# 08_Peripherals.net
KiCad netlist of a schematic drawn in Altium Designer
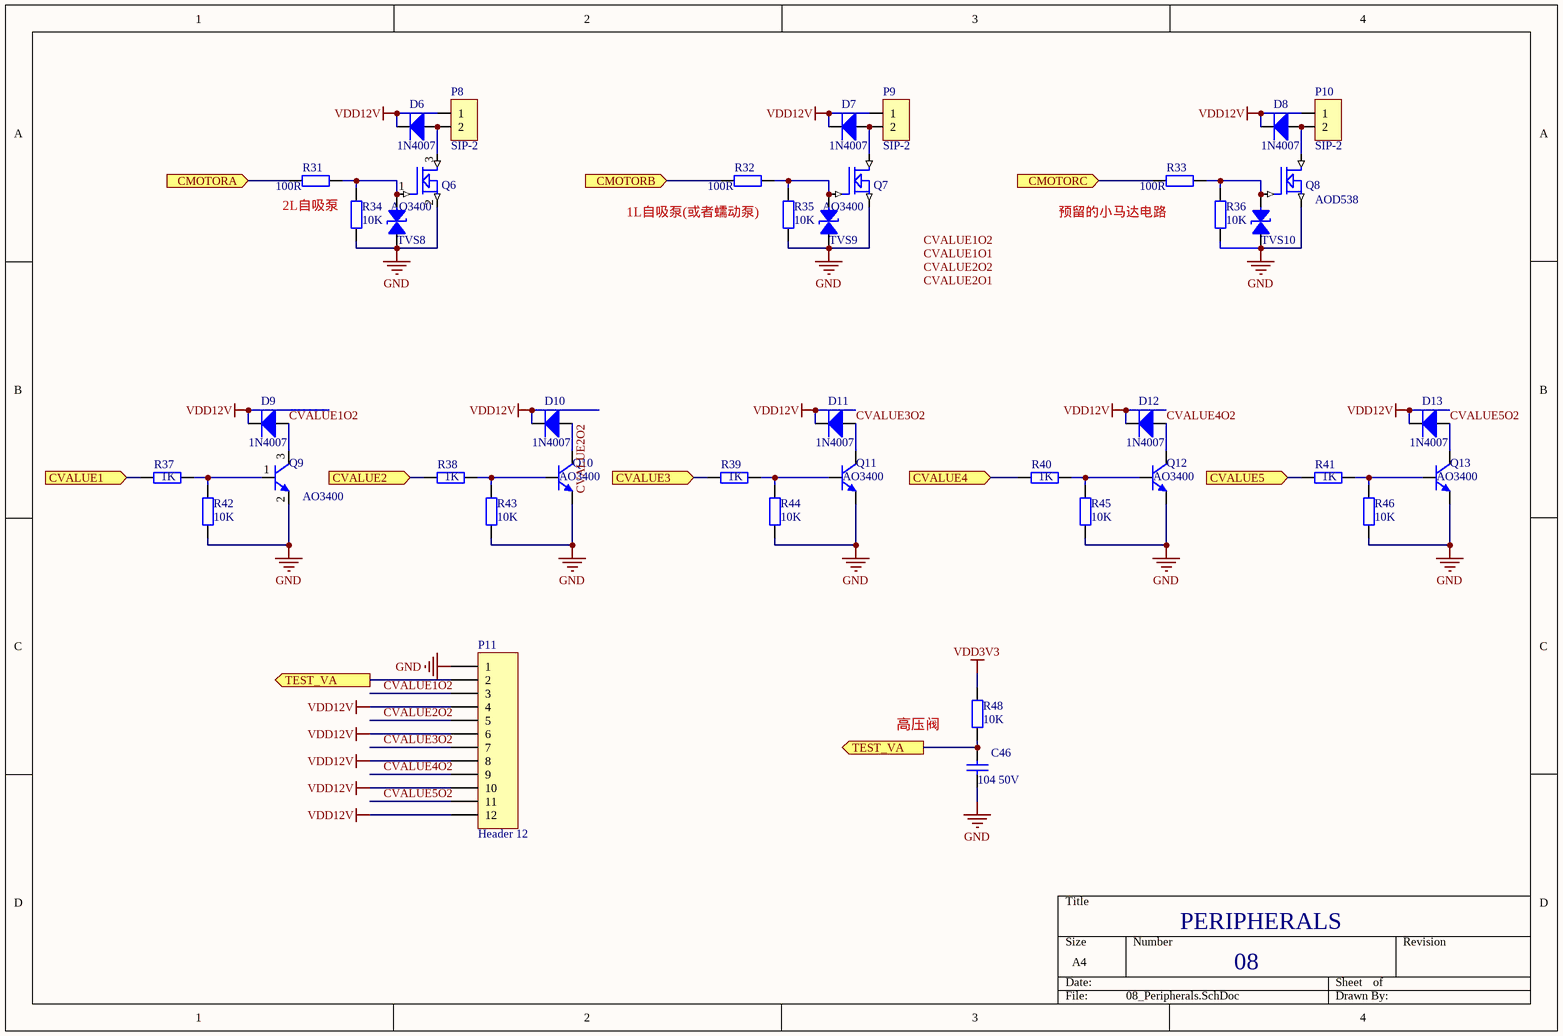
[diagram p0: 08_Peripherals.SchDoc]

(export (version "E")
  (design (tool "Eeschema 10.0.6"))
  (components
    (comp (ref "C46")
      (value "104 50V")
      (footprint "SMD-0603C")
      (description "贴片电容 10%")
      (libsource (lib "XiaoyI") (part "CAP4"))
    )
    (comp (ref "D6")
      (value "1N4007")
      (footprint "DO-214-AC")
      (description "贴片二极管")
      (libsource (lib "XiaoyI") (part "DIODE2"))
    )
    (comp (ref "D7")
      (value "1N4007")
      (footprint "DO-214-AC")
      (description "贴片二极管")
      (libsource (lib "XiaoyI") (part "DIODE2"))
    )
    (comp (ref "D8")
      (value "1N4007")
      (footprint "DO-214-AC")
      (description "贴片二极管")
      (libsource (lib "XiaoyI") (part "DIODE2"))
    )
    (comp (ref "D9")
      (value "1N4007")
      (footprint "DO-214-AC")
      (description "贴片二极管")
      (libsource (lib "XiaoyI") (part "DIODE2"))
    )
    (comp (ref "D10")
      (value "1N4007")
      (footprint "DO-214-AC")
      (description "贴片二极管")
      (libsource (lib "XiaoyI") (part "DIODE2"))
    )
    (comp (ref "D11")
      (value "1N4007")
      (footprint "DO-214-AC")
      (description "贴片二极管")
      (libsource (lib "XiaoyI") (part "DIODE2"))
    )
    (comp (ref "D12")
      (value "1N4007")
      (footprint "DO-214-AC")
      (description "贴片二极管")
      (libsource (lib "XiaoyI") (part "DIODE2"))
    )
    (comp (ref "D13")
      (value "1N4007")
      (footprint "DO-214-AC")
      (description "贴片二极管")
      (libsource (lib "XiaoyI") (part "DIODE2"))
    )
    (comp (ref "P8")
      (value "SIP-2")
      (footprint "SIP-2A")
      (description "XH2.54 2P 立贴")
      (libsource (lib "XiaoyI") (part "SIP-2"))
    )
    (comp (ref "P9")
      (value "SIP-2")
      (footprint "SIP-2A")
      (description "XH2.54 2P 立贴")
      (libsource (lib "XiaoyI") (part "SIP-2"))
    )
    (comp (ref "P10")
      (value "SIP-2")
      (footprint "VH-AW-3.96*2P")
      (description "XH2.54 2P 立贴")
      (libsource (lib "XiaoyI") (part "SIP-2"))
    )
    (comp (ref "P11")
      (value "Header 12")
      (footprint "12X2.54MMZ")
      (description "Header, 12-Pin")
      (fields (field (name "PUBLISHER") "Altium Limited"))
      (libsource (lib "Miscellaneous Connectors") (part "Header 12"))
    )
    (comp (ref "Q6")
      (value "AO3400")
      (footprint "SOT-23")
      (description "MOSFET N")
      (libsource (lib "") (part "MOSFET N_1"))
    )
    (comp (ref "Q7")
      (value "AO3400")
      (footprint "SOT-23")
      (description "MOSFET N")
      (libsource (lib "XiaoyI") (part "MOSFET N"))
    )
    (comp (ref "Q8")
      (value "AOD538")
      (footprint "TO252")
      (description "MOSFET N")
      (libsource (lib "XiaoyI") (part "MOSFET N"))
    )
    (comp (ref "Q9")
      (value "AO3400")
      (footprint "SOT-23")
      (description "三极管")
      (libsource (lib "") (part "NPN-1_1"))
    )
    (comp (ref "Q10")
      (value "AO3400")
      (footprint "SOT-23")
      (description "三极管")
      (libsource (lib "XiaoyI") (part "NPN-1"))
    )
    (comp (ref "Q11")
      (value "AO3400")
      (footprint "SOT-23")
      (description "三极管")
      (libsource (lib "XiaoyI") (part "NPN-1"))
    )
    (comp (ref "Q12")
      (value "AO3400")
      (footprint "SOT-23")
      (description "三极管")
      (libsource (lib "XiaoyI") (part "NPN-1"))
    )
    (comp (ref "Q13")
      (value "AO3400")
      (footprint "SOT-23")
      (description "三极管")
      (libsource (lib "XiaoyI") (part "NPN-1"))
    )
    (comp (ref "R31")
      (value "100R")
      (footprint "SMD-0603")
      (description "贴片电阻 5%")
      (libsource (lib "XiaoyI") (part "RES-SOP"))
    )
    (comp (ref "R32")
      (value "100R")
      (footprint "SMD-0603")
      (description "贴片电阻 5%")
      (libsource (lib "XiaoyI") (part "RES-SOP"))
    )
    (comp (ref "R33")
      (value "100R")
      (footprint "SMD-0603")
      (description "贴片电阻 5%")
      (libsource (lib "XiaoyI") (part "RES-SOP"))
    )
    (comp (ref "R34")
      (value "10K")
      (footprint "SMD-0603")
      (description "贴片电阻 5%")
      (libsource (lib "") (part "RES-SOP_1"))
    )
    (comp (ref "R35")
      (value "10K")
      (footprint "SMD-0603")
      (description "贴片电阻 5%")
      (libsource (lib "") (part "RES-SOP_1"))
    )
    (comp (ref "R36")
      (value "10K")
      (footprint "SMD-0603")
      (description "贴片电阻 5%")
      (libsource (lib "") (part "RES-SOP_1"))
    )
    (comp (ref "R37")
      (value "1K")
      (footprint "SMD-0603")
      (description "贴片电阻 5%")
      (libsource (lib "XiaoyI") (part "RES-SOP"))
    )
    (comp (ref "R38")
      (value "1K")
      (footprint "SMD-0603")
      (description "贴片电阻 5%")
      (libsource (lib "XiaoyI") (part "RES-SOP"))
    )
    (comp (ref "R39")
      (value "1K")
      (footprint "SMD-0603")
      (description "贴片电阻 5%")
      (libsource (lib "XiaoyI") (part "RES-SOP"))
    )
    (comp (ref "R40")
      (value "1K")
      (footprint "SMD-0603")
      (description "贴片电阻 5%")
      (libsource (lib "XiaoyI") (part "RES-SOP"))
    )
    (comp (ref "R41")
      (value "1K")
      (footprint "SMD-0603")
      (description "贴片电阻 5%")
      (libsource (lib "XiaoyI") (part "RES-SOP"))
    )
    (comp (ref "R42")
      (value "10K")
      (footprint "SMD-0603")
      (description "贴片电阻 5%")
      (libsource (lib "") (part "RES-SOP_1"))
    )
    (comp (ref "R43")
      (value "10K")
      (footprint "SMD-0603")
      (description "贴片电阻 5%")
      (libsource (lib "") (part "RES-SOP_1"))
    )
    (comp (ref "R44")
      (value "10K")
      (footprint "SMD-0603")
      (description "贴片电阻 5%")
      (libsource (lib "") (part "RES-SOP_1"))
    )
    (comp (ref "R45")
      (value "10K")
      (footprint "SMD-0603")
      (description "贴片电阻 5%")
      (libsource (lib "") (part "RES-SOP_1"))
    )
    (comp (ref "R46")
      (value "10K")
      (footprint "SMD-0603")
      (description "贴片电阻 5%")
      (libsource (lib "") (part "RES-SOP_1"))
    )
    (comp (ref "R48")
      (value "10K")
      (footprint "SMD-0603")
      (description "贴片电阻 5%")
      (libsource (lib "") (part "RES-SOP_2"))
    )
    (comp (ref "TVS8")
      (value "ESD5Z5.0CT1G")
      (footprint "SOD-523")
      (description "TVS")
      (libsource (lib "XiaoyI") (part "TVS-1"))
    )
    (comp (ref "TVS9")
      (value "ESD5Z5.0CT1G")
      (footprint "SOD-523")
      (description "TVS")
      (libsource (lib "XiaoyI") (part "TVS-1"))
    )
    (comp (ref "TVS10")
      (value "ESD5Z5.0CT1G")
      (footprint "SOD-523")
      (description "TVS")
      (libsource (lib "XiaoyI") (part "TVS-1"))
    )
  )
  (nets
    (net (code "1") (name "/CMOTORA") (class "Default")
      (node (ref "R31") (pin "2") (pinfunction "2_2") (pintype "passive"))
    )
    (net (code "2") (name "/CMOTORB") (class "Default")
      (node (ref "R32") (pin "2") (pinfunction "2_2") (pintype "passive"))
    )
    (net (code "3") (name "/CMOTORC") (class "Default")
      (node (ref "R33") (pin "2") (pinfunction "2_2") (pintype "passive"))
    )
    (net (code "4") (name "/CVALUE1") (class "Default")
      (node (ref "R37") (pin "2") (pinfunction "2_2") (pintype "passive"))
    )
    (net (code "6") (name "/CVALUE1O2") (class "Default")
      (node (ref "D9") (pin "1") (pinfunction "A_1") (pintype "passive"))
      (node (ref "P11") (pin "3") (pinfunction "3_3") (pintype "passive"))
      (node (ref "Q9") (pin "3") (pinfunction "C_3") (pintype "passive"))
    )
    (net (code "7") (name "/CVALUE2") (class "Default")
      (node (ref "R38") (pin "2") (pinfunction "2_2") (pintype "passive"))
    )
    (net (code "9") (name "/CVALUE2O2") (class "Default")
      (node (ref "D10") (pin "1") (pinfunction "A_1") (pintype "passive"))
      (node (ref "P11") (pin "5") (pinfunction "5_5") (pintype "passive"))
      (node (ref "Q10") (pin "3") (pinfunction "C_3") (pintype "passive"))
    )
    (net (code "10") (name "/CVALUE3") (class "Default")
      (node (ref "R39") (pin "2") (pinfunction "2_2") (pintype "passive"))
    )
    (net (code "11") (name "/CVALUE3O2") (class "Default")
      (node (ref "D11") (pin "1") (pinfunction "A_1") (pintype "passive"))
      (node (ref "P11") (pin "7") (pinfunction "7_7") (pintype "passive"))
      (node (ref "Q11") (pin "3") (pinfunction "C_3") (pintype "passive"))
    )
    (net (code "12") (name "/CVALUE4") (class "Default")
      (node (ref "R40") (pin "2") (pinfunction "2_2") (pintype "passive"))
    )
    (net (code "13") (name "/CVALUE4O2") (class "Default")
      (node (ref "D12") (pin "1") (pinfunction "A_1") (pintype "passive"))
      (node (ref "P11") (pin "9") (pinfunction "9_9") (pintype "passive"))
      (node (ref "Q12") (pin "3") (pinfunction "C_3") (pintype "passive"))
    )
    (net (code "14") (name "/CVALUE5") (class "Default")
      (node (ref "R41") (pin "2") (pinfunction "2_2") (pintype "passive"))
    )
    (net (code "15") (name "/CVALUE5O2") (class "Default")
      (node (ref "D13") (pin "1") (pinfunction "A_1") (pintype "passive"))
      (node (ref "P11") (pin "11") (pinfunction "11_11") (pintype "passive"))
      (node (ref "Q13") (pin "3") (pinfunction "C_3") (pintype "passive"))
    )
    (net (code "16") (name "/TEST_VA") (class "Default")
      (node (ref "C46") (pin "2") (pinfunction "2_2") (pintype "passive"))
      (node (ref "P11") (pin "2") (pinfunction "2_2") (pintype "passive"))
      (node (ref "R48") (pin "1") (pinfunction "1_1") (pintype "passive"))
    )
    (net (code "17") (name "GND") (class "Default")
      (node (ref "C46") (pin "1") (pinfunction "1_1") (pintype "passive"))
      (node (ref "P11") (pin "1") (pinfunction "1_1") (pintype "passive"))
      (node (ref "Q10") (pin "2") (pinfunction "E_2") (pintype "passive"))
      (node (ref "Q11") (pin "2") (pinfunction "E_2") (pintype "passive"))
      (node (ref "Q12") (pin "2") (pinfunction "E_2") (pintype "passive"))
      (node (ref "Q13") (pin "2") (pinfunction "E_2") (pintype "passive"))
      (node (ref "Q6") (pin "2") (pinfunction "S_2") (pintype "output"))
      (node (ref "Q7") (pin "2") (pinfunction "S_2") (pintype "output"))
      (node (ref "Q8") (pin "2") (pinfunction "S_2") (pintype "output"))
      (node (ref "Q9") (pin "2") (pinfunction "E_2") (pintype "passive"))
      (node (ref "R34") (pin "2") (pinfunction "2_2") (pintype "passive"))
      (node (ref "R35") (pin "2") (pinfunction "2_2") (pintype "passive"))
      (node (ref "R36") (pin "2") (pinfunction "2_2") (pintype "passive"))
      (node (ref "R42") (pin "2") (pinfunction "2_2") (pintype "passive"))
      (node (ref "R43") (pin "2") (pinfunction "2_2") (pintype "passive"))
      (node (ref "R44") (pin "2") (pinfunction "2_2") (pintype "passive"))
      (node (ref "R45") (pin "2") (pinfunction "2_2") (pintype "passive"))
      (node (ref "R46") (pin "2") (pinfunction "2_2") (pintype "passive"))
      (node (ref "TVS10") (pin "1") (pinfunction "A_1") (pintype "passive"))
      (node (ref "TVS8") (pin "1") (pinfunction "A_1") (pintype "passive"))
      (node (ref "TVS9") (pin "1") (pinfunction "A_1") (pintype "passive"))
    )
    (net (code "18") (name "Net-(D6-A)") (class "Default")
      (node (ref "D6") (pin "1") (pinfunction "A_1") (pintype "passive"))
      (node (ref "P8") (pin "2") (pinfunction "2_2") (pintype "passive"))
      (node (ref "Q6") (pin "3") (pinfunction "D_3") (pintype "input"))
    )
    (net (code "19") (name "Net-(D7-A)") (class "Default")
      (node (ref "D7") (pin "1") (pinfunction "A_1") (pintype "passive"))
      (node (ref "P9") (pin "2") (pinfunction "2_2") (pintype "passive"))
      (node (ref "Q7") (pin "3") (pinfunction "D_3") (pintype "input"))
    )
    (net (code "20") (name "Net-(D8-A)") (class "Default")
      (node (ref "D8") (pin "1") (pinfunction "A_1") (pintype "passive"))
      (node (ref "P10") (pin "2") (pinfunction "2_2") (pintype "passive"))
      (node (ref "Q8") (pin "3") (pinfunction "D_3") (pintype "input"))
    )
    (net (code "21") (name "Net-(Q6-G)") (class "Default")
      (node (ref "Q6") (pin "1") (pinfunction "G_1") (pintype "input"))
      (node (ref "R31") (pin "1") (pinfunction "1_1") (pintype "passive"))
      (node (ref "R34") (pin "1") (pinfunction "1_1") (pintype "passive"))
      (node (ref "TVS8") (pin "2") (pinfunction "B_2") (pintype "passive"))
    )
    (net (code "22") (name "Net-(Q7-G)") (class "Default")
      (node (ref "Q7") (pin "1") (pinfunction "G_1") (pintype "input"))
      (node (ref "R32") (pin "1") (pinfunction "1_1") (pintype "passive"))
      (node (ref "R35") (pin "1") (pinfunction "1_1") (pintype "passive"))
      (node (ref "TVS9") (pin "2") (pinfunction "B_2") (pintype "passive"))
    )
    (net (code "23") (name "Net-(Q8-G)") (class "Default")
      (node (ref "Q8") (pin "1") (pinfunction "G_1") (pintype "input"))
      (node (ref "R33") (pin "1") (pinfunction "1_1") (pintype "passive"))
      (node (ref "R36") (pin "1") (pinfunction "1_1") (pintype "passive"))
      (node (ref "TVS10") (pin "2") (pinfunction "B_2") (pintype "passive"))
    )
    (net (code "24") (name "Net-(Q9-B)") (class "Default")
      (node (ref "Q9") (pin "1") (pinfunction "B_1") (pintype "passive"))
      (node (ref "R37") (pin "1") (pinfunction "1_1") (pintype "passive"))
      (node (ref "R42") (pin "1") (pinfunction "1_1") (pintype "passive"))
    )
    (net (code "25") (name "Net-(Q10-B)") (class "Default")
      (node (ref "Q10") (pin "1") (pinfunction "B_1") (pintype "passive"))
      (node (ref "R38") (pin "1") (pinfunction "1_1") (pintype "passive"))
      (node (ref "R43") (pin "1") (pinfunction "1_1") (pintype "passive"))
    )
    (net (code "26") (name "Net-(Q11-B)") (class "Default")
      (node (ref "Q11") (pin "1") (pinfunction "B_1") (pintype "passive"))
      (node (ref "R39") (pin "1") (pinfunction "1_1") (pintype "passive"))
      (node (ref "R44") (pin "1") (pinfunction "1_1") (pintype "passive"))
    )
    (net (code "27") (name "Net-(Q12-B)") (class "Default")
      (node (ref "Q12") (pin "1") (pinfunction "B_1") (pintype "passive"))
      (node (ref "R40") (pin "1") (pinfunction "1_1") (pintype "passive"))
      (node (ref "R45") (pin "1") (pinfunction "1_1") (pintype "passive"))
    )
    (net (code "28") (name "Net-(Q13-B)") (class "Default")
      (node (ref "Q13") (pin "1") (pinfunction "B_1") (pintype "passive"))
      (node (ref "R41") (pin "1") (pinfunction "1_1") (pintype "passive"))
      (node (ref "R46") (pin "1") (pinfunction "1_1") (pintype "passive"))
    )
    (net (code "29") (name "VDD3V3") (class "Default")
      (node (ref "R48") (pin "2") (pinfunction "2_2") (pintype "passive"))
    )
    (net (code "30") (name "VDD12V") (class "Default")
      (node (ref "D10") (pin "2") (pinfunction "K_2") (pintype "passive"))
      (node (ref "D11") (pin "2") (pinfunction "K_2") (pintype "passive"))
      (node (ref "D12") (pin "2") (pinfunction "K_2") (pintype "passive"))
      (node (ref "D13") (pin "2") (pinfunction "K_2") (pintype "passive"))
      (node (ref "D6") (pin "2") (pinfunction "K_2") (pintype "passive"))
      (node (ref "D7") (pin "2") (pinfunction "K_2") (pintype "passive"))
      (node (ref "D8") (pin "2") (pinfunction "K_2") (pintype "passive"))
      (node (ref "D9") (pin "2") (pinfunction "K_2") (pintype "passive"))
      (node (ref "P10") (pin "1") (pinfunction "1_1") (pintype "passive"))
      (node (ref "P11") (pin "10") (pinfunction "10_10") (pintype "passive"))
      (node (ref "P11") (pin "12") (pinfunction "12_12") (pintype "passive"))
      (node (ref "P11") (pin "4") (pinfunction "4_4") (pintype "passive"))
      (node (ref "P11") (pin "6") (pinfunction "6_6") (pintype "passive"))
      (node (ref "P11") (pin "8") (pinfunction "8_8") (pintype "passive"))
      (node (ref "P8") (pin "1") (pinfunction "1_1") (pintype "passive"))
      (node (ref "P9") (pin "1") (pinfunction "1_1") (pintype "passive"))
    )
  )
)
